# Power.net
KiCad netlist of a schematic drawn in Altium Designer
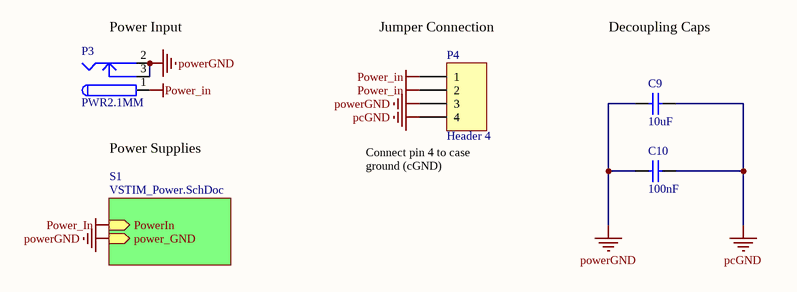
[diagram p0: Power.SchDoc]

(export (version "E")
  (design (tool "Eeschema 10.0.6"))
  (components
    (comp (ref "C9")
      (value "10uF")
      (footprint "Thesis_Testboard_V1I1:C0805")
      (description "CAP 10UF")
      (fields
        (field (name "MANUFACTURER") "Samsung Electro-Mechanics")
        (field (name "MANUFACTURER PART NUMBER") "CL21A106KAYNNNE")
      )
      (libsource (lib "standard_components") (part "C2012X5R1E106K085AC"))
    )
    (comp (ref "C10")
      (value "GRM21BR71H104KA01L")
      (footprint "CAPC2013X135X45ML10T25")
      (description "Chip Capacitor, 0.1 uF, +/- 10%, 50 V, -55 to 125 degC, 0805 (2012 Metric), RoHS, Tape and Reel")
      (fields
        (field (name "VOLTAGE") "50V")
        (field (name "CAPACITANCE") "100nF")
        (field (name "TOLERANCE") "10%")
      )
      (libsource (lib "Altium Content Vault") (part "CAP-NP-2"))
    )
    (comp (ref "P3")
      (value "PWR2.1MM")
      (footprint "Thesis_Testboard_V1I1:POWER2.1MM")
      (description "PJ-002AH")
      (fields (field (name "MANUFACTURER") "CUI"))
      (libsource (lib "Thesis_Testboard_V1I1") (part "PWR2.1MM"))
    )
    (comp (ref "P4")
      (value "Header 4")
      (footprint "on_shore_rising_clamp:OSTVN04A150")
      (description "Header, 4-Pin")
      (fields
        (field (name "MANUFACTURER") "On Shore Technology Inc.")
        (field (name "MANUFACTURER PART NUMBER") "OSTVN04A150")
        (field (name "PUBLISHER") "Altium Limited")
      )
      (libsource (lib "standard_components") (part "Header 4"))
    )
  )
  (nets
    (net (code "2") (name "Power_in") (class "Default")
      (node (ref "P3") (pin "1") (pinfunction "1_1") (pintype "power_in"))
      (node (ref "P4") (pin "1") (pinfunction "1_1") (pintype "passive"))
      (node (ref "P4") (pin "2") (pinfunction "2_2") (pintype "passive"))
    )
    (net (code "3") (name "pcGND") (class "Default")
      (node (ref "C10") (pin "1") (pinfunction "1_1") (pintype "passive"))
      (node (ref "C9") (pin "1") (pinfunction "1_1") (pintype "passive"))
      (node (ref "P4") (pin "4") (pinfunction "4_4") (pintype "passive"))
    )
    (net (code "4") (name "powerGND") (class "Default")
      (node (ref "C10") (pin "2") (pinfunction "2_2") (pintype "passive"))
      (node (ref "C9") (pin "2") (pinfunction "2_2") (pintype "passive"))
      (node (ref "P3") (pin "2") (pintype "power_in"))
      (node (ref "P3") (pin "3") (pinfunction "3_3") (pintype "power_in"))
      (node (ref "P4") (pin "3") (pinfunction "3_3") (pintype "passive"))
    )
  )
)
